# Arduino_Board.net
KiCad netlist of a schematic drawn in Altium Designer
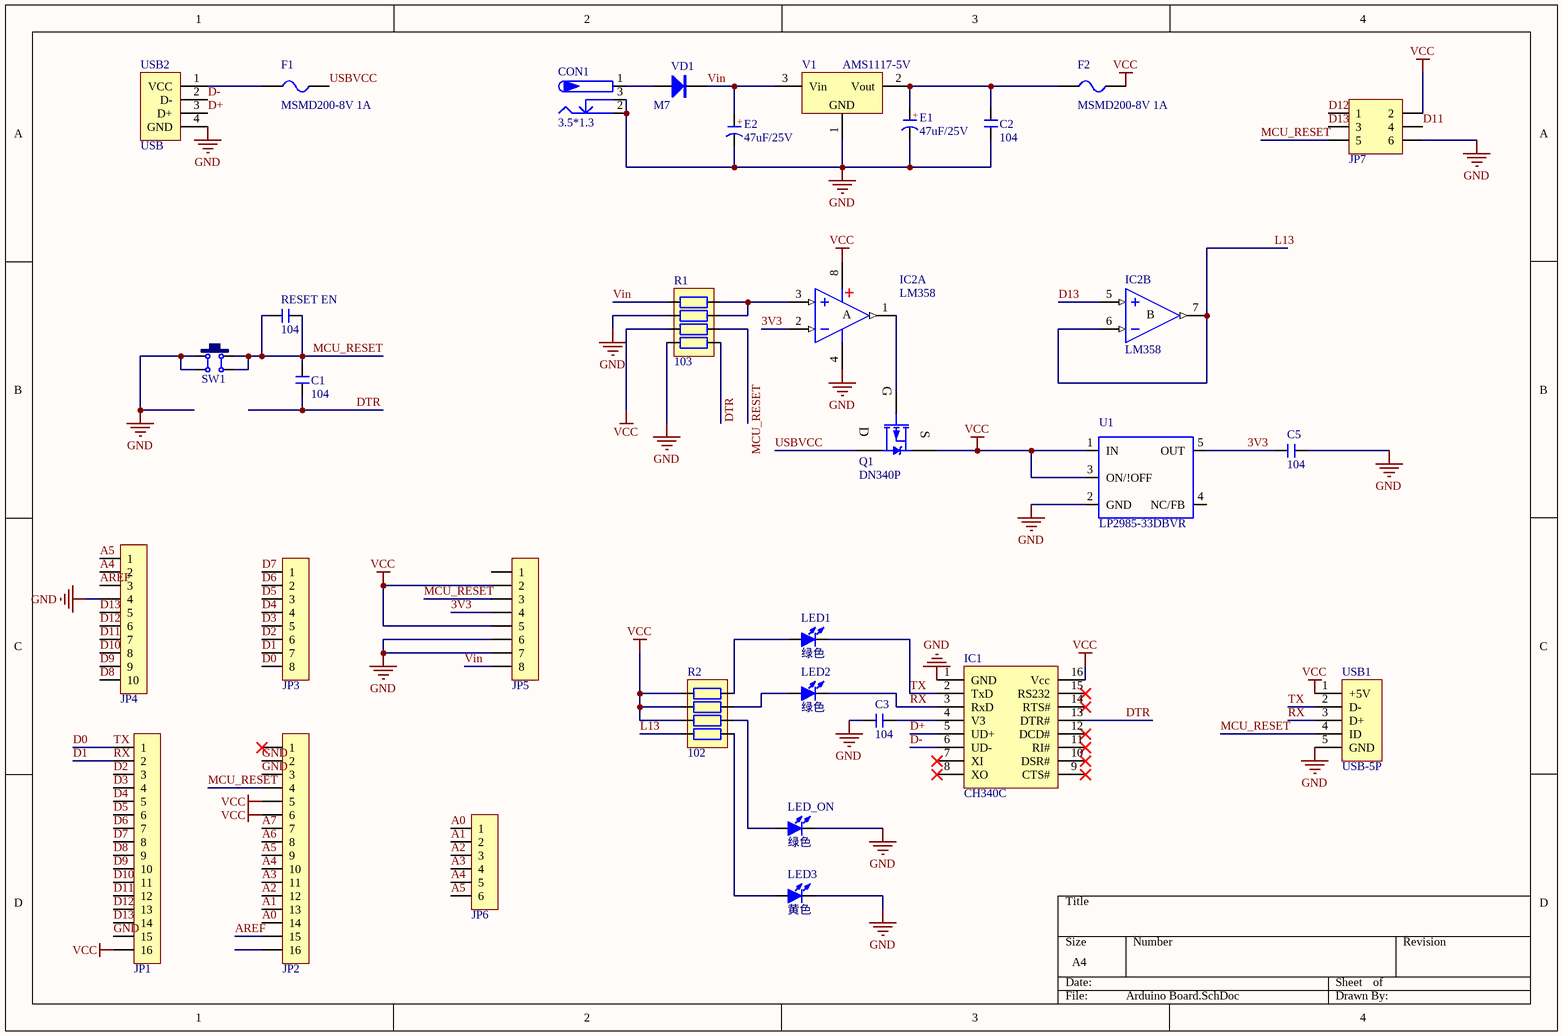
[diagram p0: Arduino Board.SchDoc]

(export (version "E")
  (design (tool "Eeschema 10.0.6"))
  (components
    (comp (ref "C1")
      (value "104")
      (footprint "C 0603")
      (description "无极性贴片电容")
      (fields (field (name "版权归属") "源创客"))
      (libsource (lib "电阻-电容-电感") (part "C"))
    )
    (comp (ref "C2")
      (value "104")
      (footprint "C 0603")
      (description "无极性贴片电容")
      (fields (field (name "版权归属") "源创客"))
      (libsource (lib "电阻-电容-电感") (part "C"))
    )
    (comp (ref "C3")
      (value "104")
      (footprint "C 0603")
      (description "无极性贴片电容")
      (fields (field (name "版权归属") "源创客"))
      (libsource (lib "电阻-电容-电感") (part "C"))
    )
    (comp (ref "C5")
      (value "104")
      (footprint "C 0603")
      (description "无极性贴片电容")
      (fields (field (name "版权归属") "源创客"))
      (libsource (lib "电阻-电容-电感") (part "C"))
    )
    (comp (ref "CON1")
      (value "3.5*1.3")
      (footprint "DC-005")
      (description "低压电源接口")
      (fields (field (name "版权归属") "源创客"))
      (libsource (lib "接口类") (part "P-DC"))
    )
    (comp (ref "E1")
      (value "47uF/25V")
      (footprint "CM D(6.3*5.4)")
      (description "贴片电解电容")
      (fields (field (name "版权归属") "源创客"))
      (libsource (lib "电阻-电容-电感") (part "C-CM"))
    )
    (comp (ref "E2")
      (value "47uF/25V")
      (footprint "CM D(6.3*5.4)")
      (description "贴片电解电容")
      (fields (field (name "版权归属") "源创客"))
      (libsource (lib "电阻-电容-电感") (part "C-CM"))
    )
    (comp (ref "F1")
      (value "MSMD200-8V 1A")
      (footprint "FU 1812")
      (description "贴片保险丝")
      (fields (field (name "版权归属") "源创客"))
      (libsource (lib "保险丝-晶振") (part "FU"))
    )
    (comp (ref "F2")
      (value "MSMD200-8V 1A")
      (footprint "FU 1812")
      (description "贴片保险丝")
      (fields (field (name "版权归属") "源创客"))
      (libsource (lib "保险丝-晶振") (part "FU"))
    )
    (comp (ref "IC1")
      (value "CH340C")
      (footprint "SOP16_L")
      (description "串口转USB")
      (fields (field (name "版权归属") "源创客"))
      (libsource (lib "IC芯片") (part "CH340G"))
    )
    (comp (ref "IC2")
      (value "LM358")
      (footprint "MSOP8_L")
      (description "双路运放")
      (fields (field (name "版权归属") "源创客"))
      (libsource (lib "IC芯片") (part "LM358"))
    )
    (comp (ref "JP1")
      (value "HDR-1X16")
      (footprint "HDR-1X16_M")
      (description "16P接插件")
      (fields (field (name "版权归属") "源创客"))
      (libsource (lib "接插件") (part "Header 16"))
    )
    (comp (ref "JP2")
      (value "HDR-1X16")
      (footprint "HDR-1X16_M")
      (description "16P接插件")
      (fields (field (name "版权归属") "源创客"))
      (libsource (lib "接插件") (part "Header 16"))
    )
    (comp (ref "JP3")
      (value "HDR-1X8")
      (footprint "HDR-1X8_M")
      (description "8P接插件")
      (fields (field (name "版权归属") "源创客"))
      (libsource (lib "接插件") (part "Header 8"))
    )
    (comp (ref "JP4")
      (value "HDR-1X10")
      (footprint "HDR-1X10_M")
      (description "10P接插件")
      (fields (field (name "版权归属") "源创客"))
      (libsource (lib "接插件") (part "Header 10"))
    )
    (comp (ref "JP5")
      (value "HDR-1X8")
      (footprint "HDR-1X8_M")
      (description "8P接插件")
      (fields (field (name "版权归属") "源创客"))
      (libsource (lib "接插件") (part "Header 8"))
    )
    (comp (ref "JP6")
      (value "HDR-1X6")
      (footprint "HDR-1X6_M")
      (description "6P接插件")
      (fields (field (name "版权归属") "源创客"))
      (libsource (lib "接插件") (part "Header 6"))
    )
    (comp (ref "JP7")
      (value "Header3X2")
      (footprint "HDR-3X2")
      (description "3*2P接插件")
      (fields (field (name "版权归属") "源创客"))
      (libsource (lib "接插件") (part "Header 3X2"))
    )
    (comp (ref "LED1")
      (value "绿色")
      (footprint "LED 0603B")
      (description "贴片LED")
      (fields (field (name "版权归属") "源创客"))
      (libsource (lib "LED") (part "LED-SMD"))
    )
    (comp (ref "LED2")
      (value "绿色")
      (footprint "LED 0603B")
      (description "贴片LED")
      (fields (field (name "版权归属") "源创客"))
      (libsource (lib "LED") (part "LED-SMD"))
    )
    (comp (ref "LED3")
      (value "黄色")
      (footprint "LED 0603B")
      (description "贴片LED")
      (fields (field (name "版权归属") "源创客"))
      (libsource (lib "LED") (part "LED-SMD"))
    )
    (comp (ref "LED_ON")
      (value "绿色")
      (footprint "LED 0603B")
      (description "贴片LED")
      (fields (field (name "版权归属") "源创客"))
      (libsource (lib "LED") (part "LED-SMD"))
    )
    (comp (ref "Q1")
      (value "DN340P")
      (footprint "SOT23-3N")
      (description "P沟道场效应管")
      (fields (field (name "版权归属") "源创客"))
      (libsource (lib "场效应管-可控硅") (part "SI2301"))
    )
    (comp (ref "R1")
      (value "103")
      (footprint "RCA-8P4R-0603")
      (description "贴片网络排阻")
      (fields (field (name "版权归属") "源创客"))
      (libsource (lib "电阻-电容-电感") (part "R-8P4R"))
    )
    (comp (ref "R2")
      (value "102")
      (footprint "RCA-8P4R-0603")
      (description "贴片网络排阻")
      (fields (field (name "版权归属") "源创客"))
      (libsource (lib "电阻-电容-电感") (part "R-8P4R"))
    )
    (comp (ref "RESET EN")
      (value "104")
      (footprint "C 0603")
      (description "无极性贴片电容")
      (fields (field (name "版权归属") "源创客"))
      (libsource (lib "电阻-电容-电感") (part "C"))
    )
    (comp (ref "SW1")
      (value "6x6x5")
      (footprint "TSW SMD-6*6*4.3")
      (description "贴片6x6轻触开关")
      (fields (field (name "版权归属") "源创客"))
      (libsource (lib "按键-开关") (part "TSW SMD-6x6"))
    )
    (comp (ref "U1")
      (value "LP2985-33DBVR")
      (footprint "SOT23-5L")
      (libsource (lib "*") (part "LP2985-XXDBVR33"))
    )
    (comp (ref "USB1")
      (value "USB-5P")
      (footprint "USB-MICRO_D")
      (description "微型USB母座")
      (fields (field (name "版权归属") "源创客"))
      (libsource (lib "接口类") (part "USB-5P"))
    )
    (comp (ref "USB2")
      (value "USB")
      (footprint "USB-B/S_A")
      (description "USB-B型母接口")
      (fields (field (name "版权归属") "源创客"))
      (libsource (lib "接口类") (part "USB-B/S"))
    )
    (comp (ref "V1")
      (value "AMS1117-5V")
      (footprint "SOT223_N")
      (description "三端稳压芯片")
      (fields (field (name "版权归属") "源创客"))
      (libsource (lib "IC芯片") (part "AMS1117"))
    )
    (comp (ref "VD1")
      (value "M7")
      (footprint "SMA")
      (description "整流二极管")
      (fields (field (name "版权归属") "源创客"))
      (libsource (lib "二极管-整流桥") (part "M7"))
    )
  )
  (nets
    (net (code "1") (name "/3V3") (class "Default")
      (node (ref "C5") (pin "1") (pinfunction "1_1") (pintype "passive"))
      (node (ref "IC2") (pin "2") (pinfunction "IN-_2") (pintype "input"))
      (node (ref "JP5") (pin "4") (pinfunction "4_4") (pintype "passive"))
      (node (ref "U1") (pin "5") (pinfunction "OUT_5") (pintype "passive"))
    )
    (net (code "2") (name "/A0") (class "Default")
      (node (ref "JP2") (pin "14") (pinfunction "14_14") (pintype "passive"))
      (node (ref "JP6") (pin "1") (pinfunction "1_1") (pintype "passive"))
    )
    (net (code "3") (name "/A1") (class "Default")
      (node (ref "JP2") (pin "13") (pinfunction "13_13") (pintype "passive"))
      (node (ref "JP6") (pin "2") (pinfunction "2_2") (pintype "passive"))
    )
    (net (code "4") (name "/A2") (class "Default")
      (node (ref "JP2") (pin "12") (pinfunction "12_12") (pintype "passive"))
      (node (ref "JP6") (pin "3") (pinfunction "3_3") (pintype "passive"))
    )
    (net (code "5") (name "/A3") (class "Default")
      (node (ref "JP2") (pin "11") (pinfunction "11_11") (pintype "passive"))
      (node (ref "JP6") (pin "4") (pinfunction "4_4") (pintype "passive"))
    )
    (net (code "6") (name "/A4") (class "Default")
      (node (ref "JP2") (pin "10") (pinfunction "10_10") (pintype "passive"))
      (node (ref "JP4") (pin "2") (pinfunction "2_2") (pintype "passive"))
      (node (ref "JP6") (pin "5") (pinfunction "5_5") (pintype "passive"))
    )
    (net (code "7") (name "/A5") (class "Default")
      (node (ref "JP2") (pin "9") (pinfunction "9_9") (pintype "passive"))
      (node (ref "JP4") (pin "1") (pinfunction "1_1") (pintype "passive"))
      (node (ref "JP6") (pin "6") (pinfunction "6_6") (pintype "passive"))
    )
    (net (code "8") (name "/A6") (class "Default")
      (node (ref "JP2") (pin "8") (pinfunction "8_8") (pintype "passive"))
    )
    (net (code "9") (name "/A7") (class "Default")
      (node (ref "JP2") (pin "7") (pinfunction "7_7") (pintype "passive"))
    )
    (net (code "10") (name "/AREF") (class "Default")
      (node (ref "JP2") (pin "15") (pinfunction "15_15") (pintype "passive"))
      (node (ref "JP4") (pin "3") (pinfunction "3_3") (pintype "passive"))
    )
    (net (code "11") (name "/D+") (class "Default")
      (node (ref "IC1") (pin "5") (pinfunction "UD+_5") (pintype "passive"))
      (node (ref "USB2") (pin "3") (pinfunction "D+_3") (pintype "passive"))
    )
    (net (code "12") (name "/D-") (class "Default")
      (node (ref "IC1") (pin "6") (pinfunction "UD-_6") (pintype "passive"))
      (node (ref "USB2") (pin "2") (pinfunction "D-_2") (pintype "passive"))
    )
    (net (code "13") (name "/D0") (class "Default")
      (node (ref "IC1") (pin "2") (pinfunction "TxD_2") (pintype "passive"))
      (node (ref "JP1") (pin "1") (pinfunction "1_1") (pintype "passive"))
      (node (ref "JP3") (pin "8") (pinfunction "8_8") (pintype "passive"))
      (node (ref "LED1") (pin "2") (pinfunction "K_2") (pintype "passive"))
      (node (ref "USB1") (pin "2") (pinfunction "D-_2") (pintype "passive"))
    )
    (net (code "14") (name "/D1") (class "Default")
      (node (ref "IC1") (pin "3") (pinfunction "RxD_3") (pintype "passive"))
      (node (ref "JP1") (pin "2") (pinfunction "2_2") (pintype "passive"))
      (node (ref "JP3") (pin "7") (pinfunction "7_7") (pintype "passive"))
      (node (ref "LED2") (pin "2") (pinfunction "K_2") (pintype "passive"))
      (node (ref "USB1") (pin "3") (pinfunction "D+_3") (pintype "passive"))
    )
    (net (code "15") (name "/D2") (class "Default")
      (node (ref "JP1") (pin "3") (pinfunction "3_3") (pintype "passive"))
      (node (ref "JP3") (pin "6") (pinfunction "6_6") (pintype "passive"))
    )
    (net (code "16") (name "/D3") (class "Default")
      (node (ref "JP1") (pin "4") (pinfunction "4_4") (pintype "passive"))
      (node (ref "JP3") (pin "5") (pinfunction "5_5") (pintype "passive"))
    )
    (net (code "17") (name "/D4") (class "Default")
      (node (ref "JP1") (pin "5") (pinfunction "5_5") (pintype "passive"))
      (node (ref "JP3") (pin "4") (pinfunction "4_4") (pintype "passive"))
    )
    (net (code "18") (name "/D5") (class "Default")
      (node (ref "JP1") (pin "6") (pinfunction "6_6") (pintype "passive"))
      (node (ref "JP3") (pin "3") (pinfunction "3_3") (pintype "passive"))
    )
    (net (code "19") (name "/D6") (class "Default")
      (node (ref "JP1") (pin "7") (pinfunction "7_7") (pintype "passive"))
      (node (ref "JP3") (pin "2") (pinfunction "2_2") (pintype "passive"))
    )
    (net (code "20") (name "/D7") (class "Default")
      (node (ref "JP1") (pin "8") (pinfunction "8_8") (pintype "passive"))
      (node (ref "JP3") (pin "1") (pinfunction "1_1") (pintype "passive"))
    )
    (net (code "21") (name "/D8") (class "Default")
      (node (ref "JP1") (pin "9") (pinfunction "9_9") (pintype "passive"))
      (node (ref "JP4") (pin "10") (pinfunction "10_10") (pintype "passive"))
    )
    (net (code "22") (name "/D9") (class "Default")
      (node (ref "JP1") (pin "10") (pinfunction "10_10") (pintype "passive"))
      (node (ref "JP4") (pin "9") (pinfunction "9_9") (pintype "passive"))
    )
    (net (code "23") (name "/D10") (class "Default")
      (node (ref "JP1") (pin "11") (pinfunction "11_11") (pintype "passive"))
      (node (ref "JP4") (pin "8") (pinfunction "8_8") (pintype "passive"))
    )
    (net (code "24") (name "/D11") (class "Default")
      (node (ref "JP1") (pin "12") (pinfunction "12_12") (pintype "passive"))
      (node (ref "JP4") (pin "7") (pinfunction "7_7") (pintype "passive"))
      (node (ref "JP7") (pin "4") (pinfunction "4_4") (pintype "passive"))
    )
    (net (code "25") (name "/D12") (class "Default")
      (node (ref "JP1") (pin "13") (pinfunction "13_13") (pintype "passive"))
      (node (ref "JP4") (pin "6") (pinfunction "6_6") (pintype "passive"))
      (node (ref "JP7") (pin "1") (pinfunction "1_1") (pintype "passive"))
    )
    (net (code "26") (name "/D13") (class "Default")
      (node (ref "IC2") (pin "5") (pinfunction "IN+_5") (pintype "input"))
      (node (ref "JP1") (pin "14") (pinfunction "14_14") (pintype "passive"))
      (node (ref "JP4") (pin "5") (pinfunction "5_5") (pintype "passive"))
      (node (ref "JP7") (pin "3") (pinfunction "3_3") (pintype "passive"))
    )
    (net (code "27") (name "/DTR") (class "Default")
      (node (ref "C1") (pin "1") (pinfunction "1_1") (pintype "passive"))
      (node (ref "IC1") (pin "13") (pinfunction "DTR#_13") (pintype "passive"))
      (node (ref "R1") (pin "5") (pinfunction "5_5") (pintype "passive"))
    )
    (net (code "28") (name "/L13") (class "Default")
      (node (ref "IC2") (pin "6") (pinfunction "IN-_6") (pintype "input"))
      (node (ref "IC2") (pin "7") (pinfunction "OUT_7") (pintype "output"))
      (node (ref "R2") (pin "4") (pinfunction "4_4") (pintype "passive"))
    )
    (net (code "29") (name "/MCU_RESET") (class "Default")
      (node (ref "C1") (pin "2") (pinfunction "2_2") (pintype "passive"))
      (node (ref "JP2") (pin "4") (pinfunction "4_4") (pintype "passive"))
      (node (ref "JP5") (pin "3") (pinfunction "3_3") (pintype "passive"))
      (node (ref "JP7") (pin "5") (pinfunction "5_5") (pintype "passive"))
      (node (ref "R1") (pin "6") (pinfunction "6_6") (pintype "passive"))
      (node (ref "RESET EN") (pin "1") (pinfunction "1_1") (pintype "passive"))
      (node (ref "RESET EN") (pin "2") (pinfunction "2_2") (pintype "passive"))
      (node (ref "SW1") (pin "2") (pinfunction "2_2") (pintype "passive"))
      (node (ref "SW1") (pin "3") (pinfunction "3_3") (pintype "passive"))
      (node (ref "USB1") (pin "4") (pinfunction "ID_4") (pintype "passive"))
    )
    (net (code "30") (name "/USBVCC") (class "Default")
      (node (ref "F1") (pin "2") (pinfunction "2_2") (pintype "passive"))
      (node (ref "Q1") (pin "3") (pinfunction "D_3") (pintype "passive"))
    )
    (net (code "31") (name "/Vin") (class "Default")
      (node (ref "E2") (pin "1") (pinfunction "A_1") (pintype "passive"))
      (node (ref "JP5") (pin "8") (pinfunction "8_8") (pintype "passive"))
      (node (ref "R1") (pin "1") (pinfunction "1_1") (pintype "passive"))
      (node (ref "V1") (pin "3") (pinfunction "Vin_3") (pintype "passive"))
      (node (ref "VD1") (pin "2") (pinfunction "K_2") (pintype "passive"))
    )
    (net (code "32") (name "GND") (class "Default")
      (node (ref "C2") (pin "1") (pinfunction "1_1") (pintype "passive"))
      (node (ref "C3") (pin "1") (pinfunction "1_1") (pintype "passive"))
      (node (ref "C5") (pin "2") (pinfunction "2_2") (pintype "passive"))
      (node (ref "CON1") (pin "2") (pintype "power_in"))
      (node (ref "CON1") (pin "3") (pintype "power_in"))
      (node (ref "E1") (pin "2") (pinfunction "K_2") (pintype "passive"))
      (node (ref "E2") (pin "2") (pinfunction "K_2") (pintype "passive"))
      (node (ref "IC1") (pin "1") (pinfunction "GND_1") (pintype "passive"))
      (node (ref "IC2") (pin "4") (pinfunction "V-_4") (pintype "power_in"))
      (node (ref "JP1") (pin "15") (pinfunction "15_15") (pintype "passive"))
      (node (ref "JP2") (pin "2") (pinfunction "2_2") (pintype "passive"))
      (node (ref "JP2") (pin "3") (pinfunction "3_3") (pintype "passive"))
      (node (ref "JP4") (pin "4") (pinfunction "4_4") (pintype "passive"))
      (node (ref "JP5") (pin "6") (pinfunction "6_6") (pintype "passive"))
      (node (ref "JP5") (pin "7") (pinfunction "7_7") (pintype "passive"))
      (node (ref "JP7") (pin "6") (pinfunction "6_6") (pintype "passive"))
      (node (ref "LED3") (pin "2") (pinfunction "K_2") (pintype "passive"))
      (node (ref "LED_ON") (pin "2") (pinfunction "K_2") (pintype "passive"))
      (node (ref "R1") (pin "2") (pinfunction "2_2") (pintype "passive"))
      (node (ref "R1") (pin "4") (pinfunction "4_4") (pintype "passive"))
      (node (ref "SW1") (pin "1") (pinfunction "1_1") (pintype "passive"))
      (node (ref "SW1") (pin "4") (pinfunction "4_4") (pintype "passive"))
      (node (ref "U1") (pin "2") (pinfunction "GND_2") (pintype "passive"))
      (node (ref "USB1") (pin "5") (pinfunction "GND_5") (pintype "passive"))
      (node (ref "USB2") (pin "4") (pinfunction "GND_4") (pintype "passive"))
      (node (ref "V1") (pin "1") (pinfunction "GND_1") (pintype "passive"))
    )
    (net (code "33") (name "Net-(E1-A)") (class "Default")
      (node (ref "C2") (pin "2") (pinfunction "2_2") (pintype "passive"))
      (node (ref "E1") (pin "1") (pinfunction "A_1") (pintype "passive"))
      (node (ref "F2") (pin "1") (pinfunction "1_1") (pintype "passive"))
      (node (ref "V1") (pin "2") (pinfunction "Vout_2") (pintype "passive"))
    )
    (net (code "34") (name "Net-(IC1-V3)") (class "Default")
      (node (ref "C3") (pin "2") (pinfunction "2_2") (pintype "passive"))
      (node (ref "IC1") (pin "4") (pinfunction "V3_4") (pintype "passive"))
    )
    (net (code "35") (name "Net-(IC2A-IN+)") (class "Default")
      (node (ref "IC2") (pin "3") (pinfunction "IN+_3") (pintype "input"))
      (node (ref "R1") (pin "7") (pinfunction "7_7") (pintype "passive"))
      (node (ref "R1") (pin "8") (pinfunction "8_8") (pintype "passive"))
    )
    (net (code "36") (name "Net-(IC2A-OUT)") (class "Default")
      (node (ref "IC2") (pin "1") (pinfunction "OUT_1") (pintype "output"))
      (node (ref "Q1") (pin "1") (pinfunction "G_1") (pintype "passive"))
    )
    (net (code "37") (name "Net-(LED1-A)") (class "Default")
      (node (ref "LED1") (pin "1") (pinfunction "A_1") (pintype "passive"))
      (node (ref "R2") (pin "8") (pinfunction "8_8") (pintype "passive"))
    )
    (net (code "38") (name "Net-(LED2-A)") (class "Default")
      (node (ref "LED2") (pin "1") (pinfunction "A_1") (pintype "passive"))
      (node (ref "R2") (pin "7") (pinfunction "7_7") (pintype "passive"))
    )
    (net (code "39") (name "Net-(LED3-A)") (class "Default")
      (node (ref "LED3") (pin "1") (pinfunction "A_1") (pintype "passive"))
      (node (ref "R2") (pin "5") (pinfunction "5_5") (pintype "passive"))
    )
    (net (code "40") (name "Net-(LED_ON-A)") (class "Default")
      (node (ref "LED_ON") (pin "1") (pinfunction "A_1") (pintype "passive"))
      (node (ref "R2") (pin "6") (pinfunction "6_6") (pintype "passive"))
    )
    (net (code "41") (name "Net-(USB2-VCC)") (class "Default")
      (node (ref "F1") (pin "1") (pinfunction "1_1") (pintype "passive"))
      (node (ref "USB2") (pin "1") (pinfunction "VCC_1") (pintype "passive"))
    )
    (net (code "42") (name "Net-(VD1-A)") (class "Default")
      (node (ref "CON1") (pin "1") (pintype "power_in"))
      (node (ref "VD1") (pin "1") (pinfunction "A_1") (pintype "passive"))
    )
    (net (code "43") (name "VCC") (class "Default")
      (node (ref "F2") (pin "2") (pinfunction "2_2") (pintype "passive"))
      (node (ref "IC1") (pin "16") (pinfunction "Vcc_16") (pintype "passive"))
      (node (ref "IC2") (pin "8") (pinfunction "V+_8") (pintype "power_in"))
      (node (ref "JP1") (pin "16") (pinfunction "16_16") (pintype "passive"))
      (node (ref "JP2") (pin "5") (pinfunction "5_5") (pintype "passive"))
      (node (ref "JP2") (pin "6") (pinfunction "6_6") (pintype "passive"))
      (node (ref "JP5") (pin "2") (pinfunction "2_2") (pintype "passive"))
      (node (ref "JP5") (pin "5") (pinfunction "5_5") (pintype "passive"))
      (node (ref "JP7") (pin "2") (pinfunction "2_2") (pintype "passive"))
      (node (ref "Q1") (pin "2") (pinfunction "S_2") (pintype "passive"))
      (node (ref "R1") (pin "3") (pinfunction "3_3") (pintype "passive"))
      (node (ref "R2") (pin "1") (pinfunction "1_1") (pintype "passive"))
      (node (ref "R2") (pin "2") (pinfunction "2_2") (pintype "passive"))
      (node (ref "R2") (pin "3") (pinfunction "3_3") (pintype "passive"))
      (node (ref "U1") (pin "1") (pinfunction "IN_1") (pintype "passive"))
      (node (ref "U1") (pin "3") (pinfunction "ON/!OFF_3") (pintype "passive"))
      (node (ref "USB1") (pin "1") (pinfunction "+5V_1") (pintype "passive"))
    )
    (net (code "44") (name "unconnected-(IC1-CTS#-Pad9)") (class "Default")
      (node (ref "IC1") (pin "9") (pinfunction "CTS#_9") (pintype "passive+no_connect"))
    )
    (net (code "45") (name "unconnected-(IC1-DCD#-Pad12)") (class "Default")
      (node (ref "IC1") (pin "12") (pinfunction "DCD#_12") (pintype "passive+no_connect"))
    )
    (net (code "46") (name "unconnected-(IC1-DSR#-Pad10)") (class "Default")
      (node (ref "IC1") (pin "10") (pinfunction "DSR#_10") (pintype "passive+no_connect"))
    )
    (net (code "47") (name "unconnected-(IC1-RI#-Pad11)") (class "Default")
      (node (ref "IC1") (pin "11") (pinfunction "RI#_11") (pintype "passive+no_connect"))
    )
    (net (code "48") (name "unconnected-(IC1-RS232-Pad15)") (class "Default")
      (node (ref "IC1") (pin "15") (pinfunction "RS232_15") (pintype "passive+no_connect"))
    )
    (net (code "49") (name "unconnected-(IC1-RTS#-Pad14)") (class "Default")
      (node (ref "IC1") (pin "14") (pinfunction "RTS#_14") (pintype "passive+no_connect"))
    )
    (net (code "50") (name "unconnected-(IC1-XI-Pad7)") (class "Default")
      (node (ref "IC1") (pin "7") (pinfunction "XI_7") (pintype "passive+no_connect"))
    )
    (net (code "51") (name "unconnected-(IC1-XO-Pad8)") (class "Default")
      (node (ref "IC1") (pin "8") (pinfunction "XO_8") (pintype "passive+no_connect"))
    )
    (net (code "52") (name "unconnected-(JP2-Pad1)") (class "Default")
      (node (ref "JP2") (pin "1") (pinfunction "1_1") (pintype "passive+no_connect"))
    )
    (net (code "53") (name "unconnected-(JP2-Pad16)") (class "Default")
      (node (ref "JP2") (pin "16") (pinfunction "16_16") (pintype "passive"))
    )
    (net (code "54") (name "unconnected-(JP5-Pad1)") (class "Default")
      (node (ref "JP5") (pin "1") (pinfunction "1_1") (pintype "passive"))
    )
    (net (code "55") (name "unconnected-(U1-NC{slash}FB-Pad4)") (class "Default")
      (node (ref "U1") (pin "4") (pinfunction "NC/FB_4") (pintype "passive"))
    )
  )
)
